# ExtendBoard.net
KiCad netlist of a schematic drawn in Altium Designer
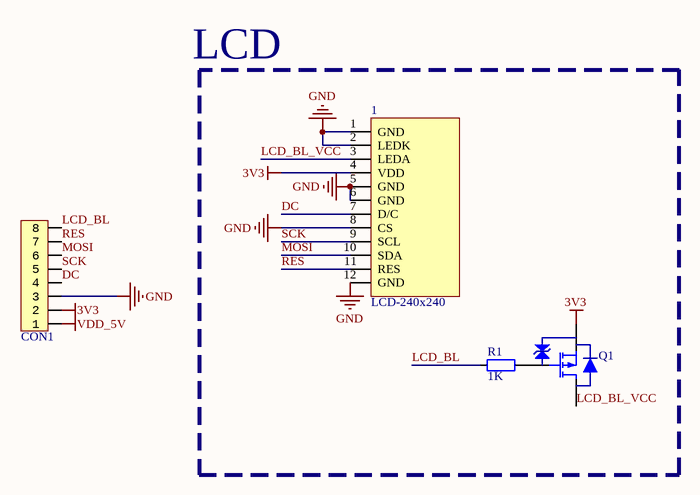
[diagram p0: ExtendBoard.SchDoc]

(export (version "E")
  (design (tool "Eeschema 10.0.6"))
  (components
    (comp (ref "1")
      (value "LCD-240x240")
      (footprint "LCD-240x240-NoHole")
      (description "显示屏")
      (libsource (lib "mLib") (part "LCD-240x240"))
    )
    (comp (ref "CON1")
      (value "FFC_0.5_8")
      (footprint "FFC_0.5_8")
      (description "FFC")
      (libsource (lib "KitSprout") (part "FFC_0.5_8"))
    )
    (comp (ref "Q1")
      (value "AO3415A")
      (footprint "SOT23-3")
      (description "MOSFET")
      (fields (field (name "PUBLISHER") "Altium Limited"))
      (libsource (lib "MyPcbLib") (part "AO3415A"))
    )
    (comp (ref "R1")
      (value "1K")
      (footprint "RES_0402")
      (description "Resistor")
      (libsource (lib "MyPcbLib") (part "电阻-0402"))
    )
  )
  (nets
    (net (code "1") (name "/DC") (class "Default")
      (node (ref "1") (pin "7") (pinfunction "D/C_7") (pintype "passive"))
      (node (ref "CON1") (pin "4") (pinfunction "4_4") (pintype "passive"))
    )
    (net (code "2") (name "/LCD_BL") (class "Default")
      (node (ref "CON1") (pin "8") (pinfunction "8_8") (pintype "passive"))
      (node (ref "R1") (pin "1") (pinfunction "1_1") (pintype "passive"))
    )
    (net (code "3") (name "/LCD_BL_VCC") (class "Default")
      (node (ref "1") (pin "3") (pinfunction "LEDA_3") (pintype "passive"))
      (node (ref "Q1") (pin "3") (pinfunction "D_3") (pintype "passive"))
    )
    (net (code "4") (name "/MOSI") (class "Default")
      (node (ref "1") (pin "10") (pinfunction "SDA_10") (pintype "passive"))
      (node (ref "CON1") (pin "6") (pinfunction "6_6") (pintype "passive"))
    )
    (net (code "5") (name "/RES") (class "Default")
      (node (ref "1") (pin "11") (pinfunction "RES_11") (pintype "passive"))
      (node (ref "CON1") (pin "7") (pinfunction "7_7") (pintype "passive"))
    )
    (net (code "6") (name "/SCK") (class "Default")
      (node (ref "1") (pin "9") (pinfunction "SCL_9") (pintype "passive"))
      (node (ref "CON1") (pin "5") (pinfunction "5_5") (pintype "passive"))
    )
    (net (code "7") (name "3V3") (class "Default")
      (node (ref "1") (pin "4") (pinfunction "VDD_4") (pintype "passive"))
      (node (ref "CON1") (pin "2") (pinfunction "2_2") (pintype "passive"))
      (node (ref "Q1") (pin "2") (pinfunction "S_2") (pintype "passive"))
    )
    (net (code "8") (name "GND") (class "Default")
      (node (ref "1") (pin "1") (pinfunction "GND_1") (pintype "passive"))
      (node (ref "1") (pin "12") (pinfunction "GND_12") (pintype "passive"))
      (node (ref "1") (pin "2") (pinfunction "LEDK_2") (pintype "passive"))
      (node (ref "1") (pin "5") (pinfunction "GND_5") (pintype "passive"))
      (node (ref "1") (pin "6") (pinfunction "GND_6") (pintype "passive"))
      (node (ref "1") (pin "8") (pinfunction "CS_8") (pintype "passive"))
      (node (ref "CON1") (pin "3") (pinfunction "3_3") (pintype "passive"))
    )
    (net (code "9") (name "Net-(Q1-G)") (class "Default")
      (node (ref "Q1") (pin "1") (pinfunction "G_1") (pintype "passive"))
      (node (ref "R1") (pin "2") (pinfunction "2_2") (pintype "passive"))
    )
    (net (code "10") (name "VDD_5V") (class "Default")
      (node (ref "CON1") (pin "1") (pinfunction "1_1") (pintype "passive"))
    )
  )
)
